# Porta_MDB.net
KiCad netlist of a schematic drawn in Altium Designer
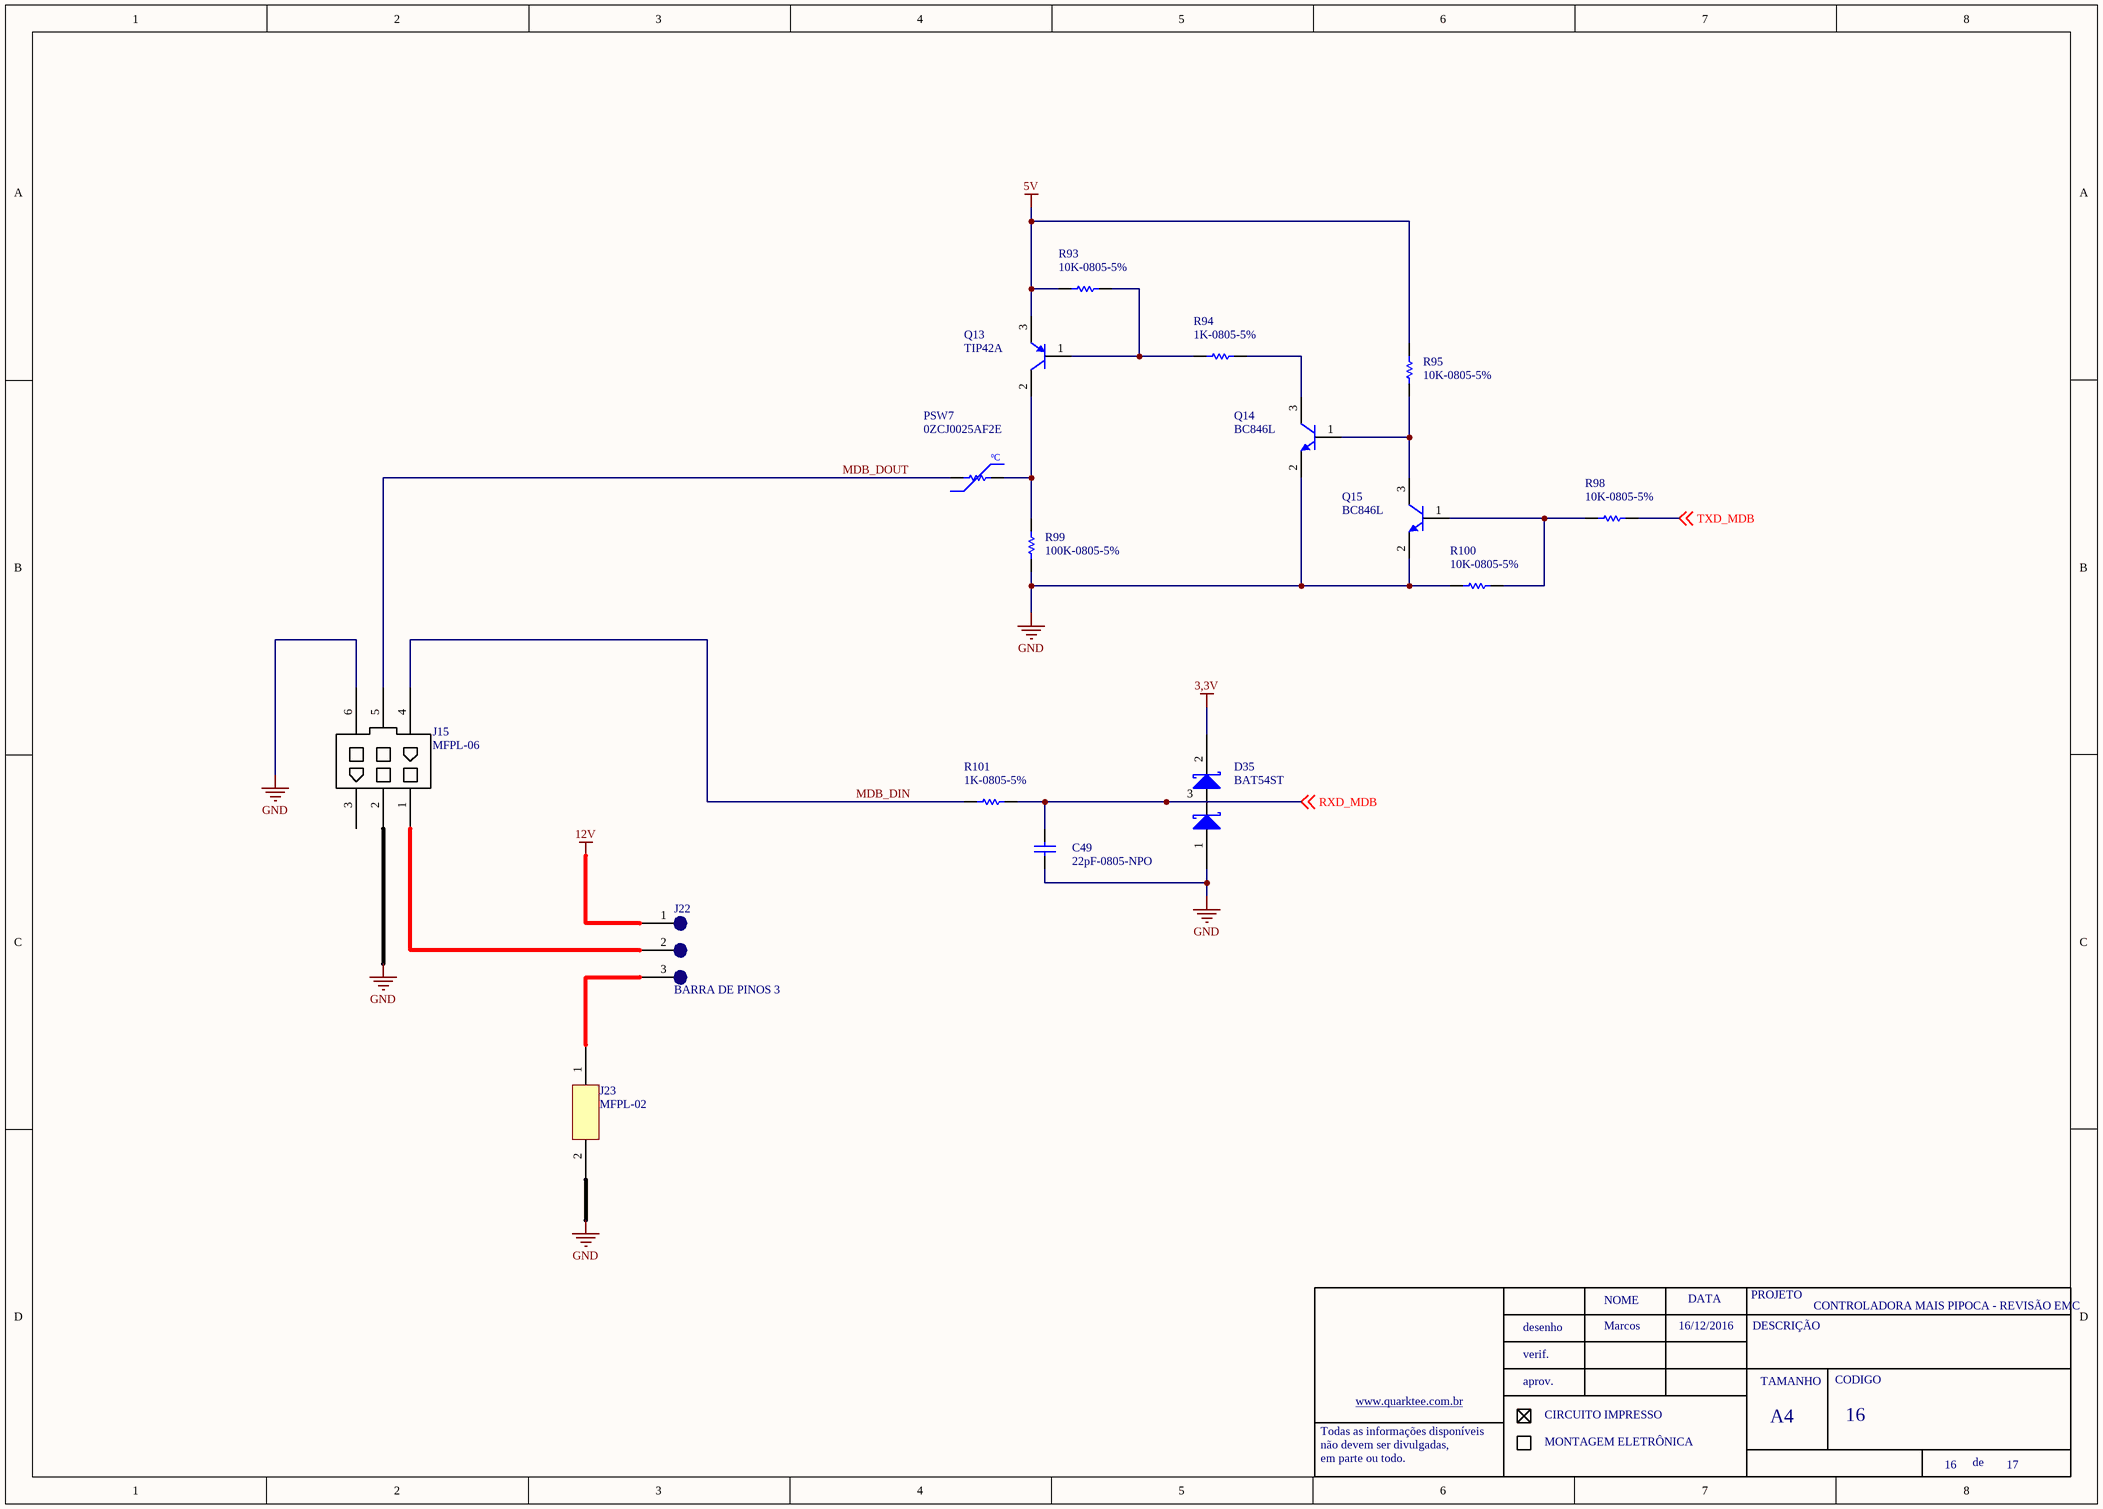
[diagram p0: Porta_MDB.SchDoc]

(export (version "E")
  (design (tool "Eeschema 10.0.6"))
  (components
    (comp (ref "C49")
      (value "22pF-0805-NPO")
      (footprint "0805-REVISADO ONDA")
      (libsource (lib "AquinoLib") (part "22pF-0805-NPO"))
    )
    (comp (ref "D35")
      (value "BAT54ST")
      (footprint "SOT23 - REVISADO ONDA")
      (libsource (lib "AquinoLib") (part "BAT54ST"))
    )
    (comp (ref "J15") (value "MFPL-06") (libsource (lib "AquinoLib") (part "MFPL-06")))
    (comp (ref "J22") (value "BARRA DE PINOS 3") (libsource (lib "ChaveDigital3") (part "JUMPER 3")))
    (comp (ref "J23") (value "MFPL-02") (libsource (lib "AquinoLib") (part "MFPL-02")))
    (comp (ref "PSW7")
      (value "0ZCJ0025AF2E")
      (footprint "1206-REVISADO ONDA")
      (description "PTC 2A-120V")
      (libsource (lib "AquinoLib") (part "PTC 2A-120V"))
    )
    (comp (ref "Q13")
      (value "TIP42A")
      (footprint "DPAK REVISADO ONDA")
      (libsource (lib "AquinoLib") (part "TIP42A"))
    )
    (comp (ref "Q14")
      (value "BC846L")
      (footprint "SOT23 - REVISADO ONDA")
      (libsource (lib "AquinoLib") (part "BC846"))
    )
    (comp (ref "Q15")
      (value "BC846L")
      (footprint "SOT23 - REVISADO ONDA")
      (libsource (lib "AquinoLib") (part "BC846"))
    )
    (comp (ref "R93")
      (value "10K-0805-5%")
      (footprint "0805-REVISADO ONDA")
      (libsource (lib "AquinoLib") (part "10K-0805-5%"))
    )
    (comp (ref "R94")
      (value "1K-0805-5%")
      (footprint "0805-REVISADO ONDA")
      (libsource (lib "AquinoLib") (part "1K-0805-5%"))
    )
    (comp (ref "R95")
      (value "10K-0805-5%")
      (footprint "0805-REVISADO ONDA")
      (libsource (lib "AquinoLib") (part "10K-0805-5%"))
    )
    (comp (ref "R98")
      (value "10K-0805-5%")
      (footprint "0805-REVISADO ONDA")
      (libsource (lib "AquinoLib") (part "10K-0805-5%"))
    )
    (comp (ref "R99")
      (value "100K-0805-5%")
      (footprint "0805-REVISADO ONDA")
      (libsource (lib "AquinoLib") (part "100K-0805-5%"))
    )
    (comp (ref "R100")
      (value "10K-0805-5%")
      (footprint "0805-REVISADO ONDA")
      (libsource (lib "AquinoLib") (part "10K-0805-5%"))
    )
    (comp (ref "R101")
      (value "1K-0805-5%")
      (footprint "0805-REVISADO ONDA")
      (libsource (lib "AquinoLib") (part "1K-0805-5%"))
    )
  )
  (nets
    (net (code "1") (name "/MDB_DIN") (class "Default")
      (node (ref "J15") (pin "4") (pinfunction "4_4") (pintype "passive"))
      (node (ref "R101") (pin "1") (pinfunction "1_1") (pintype "passive"))
    )
    (net (code "2") (name "/MDB_DOUT") (class "Default")
      (node (ref "J15") (pin "5") (pinfunction "5_5") (pintype "passive"))
      (node (ref "PSW7") (pin "1") (pinfunction "1_1") (pintype "passive"))
    )
    (net (code "3") (name "3,3V") (class "Default")
      (node (ref "D35") (pin "2") (pinfunction "2_2") (pintype "passive"))
    )
    (net (code "4") (name "5V") (class "Default")
      (node (ref "Q13") (pin "3") (pinfunction "E_3") (pintype "passive"))
      (node (ref "R93") (pin "1") (pinfunction "1_1") (pintype "passive"))
      (node (ref "R95") (pin "2") (pinfunction "2_2") (pintype "passive"))
    )
    (net (code "5") (name "12V") (class "Default")
      (node (ref "J22") (pin "1") (pinfunction "1_1") (pintype "passive"))
    )
    (net (code "6") (name "GND") (class "Default")
      (node (ref "C49") (pin "1") (pinfunction "1_1") (pintype "passive"))
      (node (ref "D35") (pin "1") (pinfunction "1_1") (pintype "passive"))
      (node (ref "J15") (pin "2") (pinfunction "2_2") (pintype "passive"))
      (node (ref "J15") (pin "6") (pinfunction "6_6") (pintype "passive"))
      (node (ref "J23") (pin "2") (pinfunction "2_2") (pintype "passive"))
      (node (ref "Q14") (pin "2") (pinfunction "E_2") (pintype "passive"))
      (node (ref "Q15") (pin "2") (pinfunction "E_2") (pintype "passive"))
      (node (ref "R100") (pin "1") (pinfunction "1_1") (pintype "passive"))
      (node (ref "R99") (pin "1") (pinfunction "1_1") (pintype "passive"))
    )
    (net (code "7") (name "Net-(J15-Pad1)") (class "Default")
      (node (ref "J15") (pin "1") (pinfunction "1_1") (pintype "passive"))
      (node (ref "J22") (pin "2") (pinfunction "2_2") (pintype "passive"))
    )
    (net (code "8") (name "Net-(J22-Pad3)") (class "Default")
      (node (ref "J22") (pin "3") (pinfunction "3_3") (pintype "passive"))
      (node (ref "J23") (pin "1") (pinfunction "1_1") (pintype "passive"))
    )
    (net (code "9") (name "Net-(Q13-B)") (class "Default")
      (node (ref "Q13") (pin "1") (pinfunction "B_1") (pintype "passive"))
      (node (ref "R93") (pin "2") (pinfunction "2_2") (pintype "passive"))
      (node (ref "R94") (pin "1") (pinfunction "1_1") (pintype "passive"))
    )
    (net (code "10") (name "Net-(Q13-C)") (class "Default")
      (node (ref "PSW7") (pin "2") (pinfunction "2_2") (pintype "passive"))
      (node (ref "Q13") (pin "2") (pinfunction "C_2") (pintype "passive"))
      (node (ref "R99") (pin "2") (pinfunction "2_2") (pintype "passive"))
    )
    (net (code "11") (name "Net-(Q14-B)") (class "Default")
      (node (ref "Q14") (pin "1") (pinfunction "B_1") (pintype "passive"))
      (node (ref "Q15") (pin "3") (pinfunction "C_3") (pintype "passive"))
      (node (ref "R95") (pin "1") (pinfunction "1_1") (pintype "passive"))
    )
    (net (code "12") (name "Net-(Q14-C)") (class "Default")
      (node (ref "Q14") (pin "3") (pinfunction "C_3") (pintype "passive"))
      (node (ref "R94") (pin "2") (pinfunction "2_2") (pintype "passive"))
    )
    (net (code "13") (name "Net-(Q15-B)") (class "Default")
      (node (ref "Q15") (pin "1") (pinfunction "B_1") (pintype "passive"))
      (node (ref "R100") (pin "2") (pinfunction "2_2") (pintype "passive"))
      (node (ref "R98") (pin "1") (pinfunction "1_1") (pintype "passive"))
    )
    (net (code "14") (name "RXD_MDB") (class "Default")
      (node (ref "C49") (pin "2") (pinfunction "2_2") (pintype "passive"))
      (node (ref "D35") (pin "3") (pinfunction "3_3") (pintype "passive"))
      (node (ref "R101") (pin "2") (pinfunction "2_2") (pintype "passive"))
    )
    (net (code "15") (name "TXD_MDB") (class "Default")
      (node (ref "R98") (pin "2") (pinfunction "2_2") (pintype "passive"))
    )
    (net (code "16") (name "unconnected-(J15-Pad3)") (class "Default")
      (node (ref "J15") (pin "3") (pinfunction "3_3") (pintype "passive"))
    )
  )
)
